# digi_pwr.net
KiCad netlist of a schematic drawn in Altium Designer
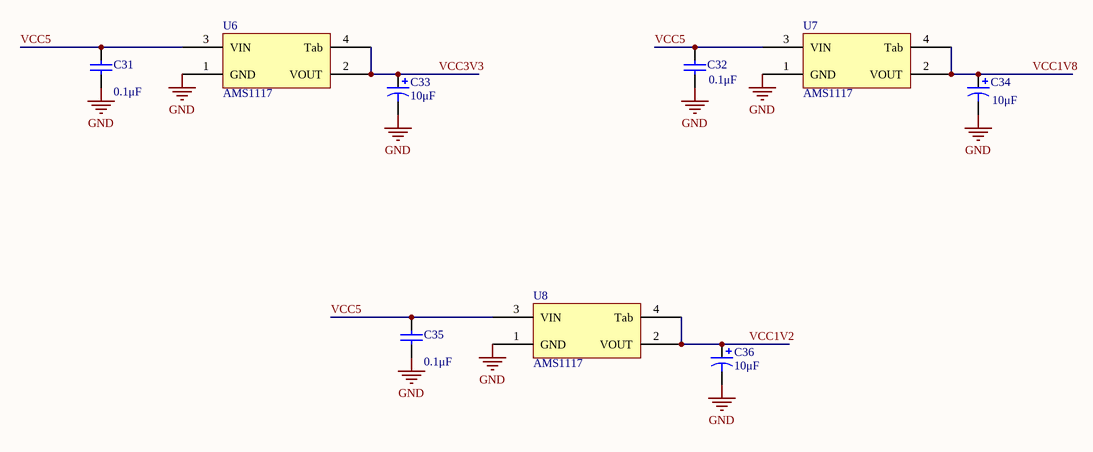
[diagram p0: digi_pwr.SchDoc]

(export (version "E")
  (design (tool "Eeschema 10.0.6"))
  (components
    (comp (ref "C31")
      (value "0.1μF")
      (footprint "1608[0603]")
      (description "Capacitor (Semiconductor SIM Model)")
      (fields (field (name "Comment") "Cap Semi") (field (name "PUBLISHER") "Altium Limited"))
      (libsource (lib "Miscellaneous Devices") (part "Cap Semi"))
    )
    (comp (ref "C32")
      (value "0.1μF")
      (footprint "1608[0603]")
      (description "Capacitor (Semiconductor SIM Model)")
      (fields (field (name "Comment") "Cap Semi") (field (name "PUBLISHER") "Altium Limited"))
      (libsource (lib "Miscellaneous Devices") (part "Cap Semi"))
    )
    (comp (ref "C33")
      (value "10μF")
      (footprint "C0805")
      (description "Polarized Capacitor (Surface Mount)")
      (fields (field (name "Comment") "Cap Pol3") (field (name "PUBLISHER") "Altium Limited"))
      (libsource (lib "Miscellaneous Devices") (part "Cap Pol3"))
    )
    (comp (ref "C34")
      (value "10μF")
      (footprint "C0805")
      (description "Polarized Capacitor (Surface Mount)")
      (fields (field (name "Comment") "Cap Pol3") (field (name "PUBLISHER") "Altium Limited"))
      (libsource (lib "Miscellaneous Devices") (part "Cap Pol3"))
    )
    (comp (ref "C35")
      (value "0.1μF")
      (footprint "1608[0603]")
      (description "Capacitor (Semiconductor SIM Model)")
      (fields (field (name "Comment") "Cap Semi") (field (name "PUBLISHER") "Altium Limited"))
      (libsource (lib "Miscellaneous Devices") (part "Cap Semi"))
    )
    (comp (ref "C36")
      (value "10μF")
      (footprint "C0805")
      (description "Polarized Capacitor (Surface Mount)")
      (fields (field (name "Comment") "Cap Pol3") (field (name "PUBLISHER") "Altium Limited"))
      (libsource (lib "Miscellaneous Devices") (part "Cap Pol3"))
    )
    (comp (ref "U6") (value "AMS1117") (footprint "SOT-223") (libsource (lib "nir_usb") (part "AMS1117")))
    (comp (ref "U7") (value "AMS1117") (footprint "SOT-223") (libsource (lib "nir_usb") (part "AMS1117")))
    (comp (ref "U8") (value "AMS1117") (footprint "SOT-223") (libsource (lib "nir_usb") (part "AMS1117")))
  )
  (nets
    (net (code "1") (name "/VCC1V2") (class "Default")
      (node (ref "C36") (pin "1") (pinfunction "1_1") (pintype "passive"))
      (node (ref "U8") (pin "2") (pinfunction "VOUT_2") (pintype "passive"))
      (node (ref "U8") (pin "4") (pinfunction "Tab_4") (pintype "passive"))
    )
    (net (code "2") (name "/VCC1V8") (class "Default")
      (node (ref "C34") (pin "1") (pinfunction "1_1") (pintype "passive"))
      (node (ref "U7") (pin "2") (pinfunction "VOUT_2") (pintype "passive"))
      (node (ref "U7") (pin "4") (pinfunction "Tab_4") (pintype "passive"))
    )
    (net (code "3") (name "/VCC3V3") (class "Default")
      (node (ref "C33") (pin "1") (pinfunction "1_1") (pintype "passive"))
      (node (ref "U6") (pin "2") (pinfunction "VOUT_2") (pintype "passive"))
      (node (ref "U6") (pin "4") (pinfunction "Tab_4") (pintype "passive"))
    )
    (net (code "4") (name "/VCC5") (class "Default")
      (node (ref "C31") (pin "2") (pinfunction "2_2") (pintype "passive"))
      (node (ref "C32") (pin "2") (pinfunction "2_2") (pintype "passive"))
      (node (ref "C35") (pin "2") (pinfunction "2_2") (pintype "passive"))
      (node (ref "U6") (pin "3") (pinfunction "VIN_3") (pintype "passive"))
      (node (ref "U7") (pin "3") (pinfunction "VIN_3") (pintype "passive"))
      (node (ref "U8") (pin "3") (pinfunction "VIN_3") (pintype "passive"))
    )
    (net (code "5") (name "GND") (class "Default")
      (node (ref "C31") (pin "1") (pinfunction "1_1") (pintype "passive"))
      (node (ref "C32") (pin "1") (pinfunction "1_1") (pintype "passive"))
      (node (ref "C33") (pin "2") (pinfunction "2_2") (pintype "passive"))
      (node (ref "C34") (pin "2") (pinfunction "2_2") (pintype "passive"))
      (node (ref "C35") (pin "1") (pinfunction "1_1") (pintype "passive"))
      (node (ref "C36") (pin "2") (pinfunction "2_2") (pintype "passive"))
      (node (ref "U6") (pin "1") (pinfunction "GND_1") (pintype "passive"))
      (node (ref "U7") (pin "1") (pinfunction "GND_1") (pintype "passive"))
      (node (ref "U8") (pin "1") (pinfunction "GND_1") (pintype "passive"))
    )
  )
)
